# R002B.net
KiCad netlist of a schematic drawn in EAGLE
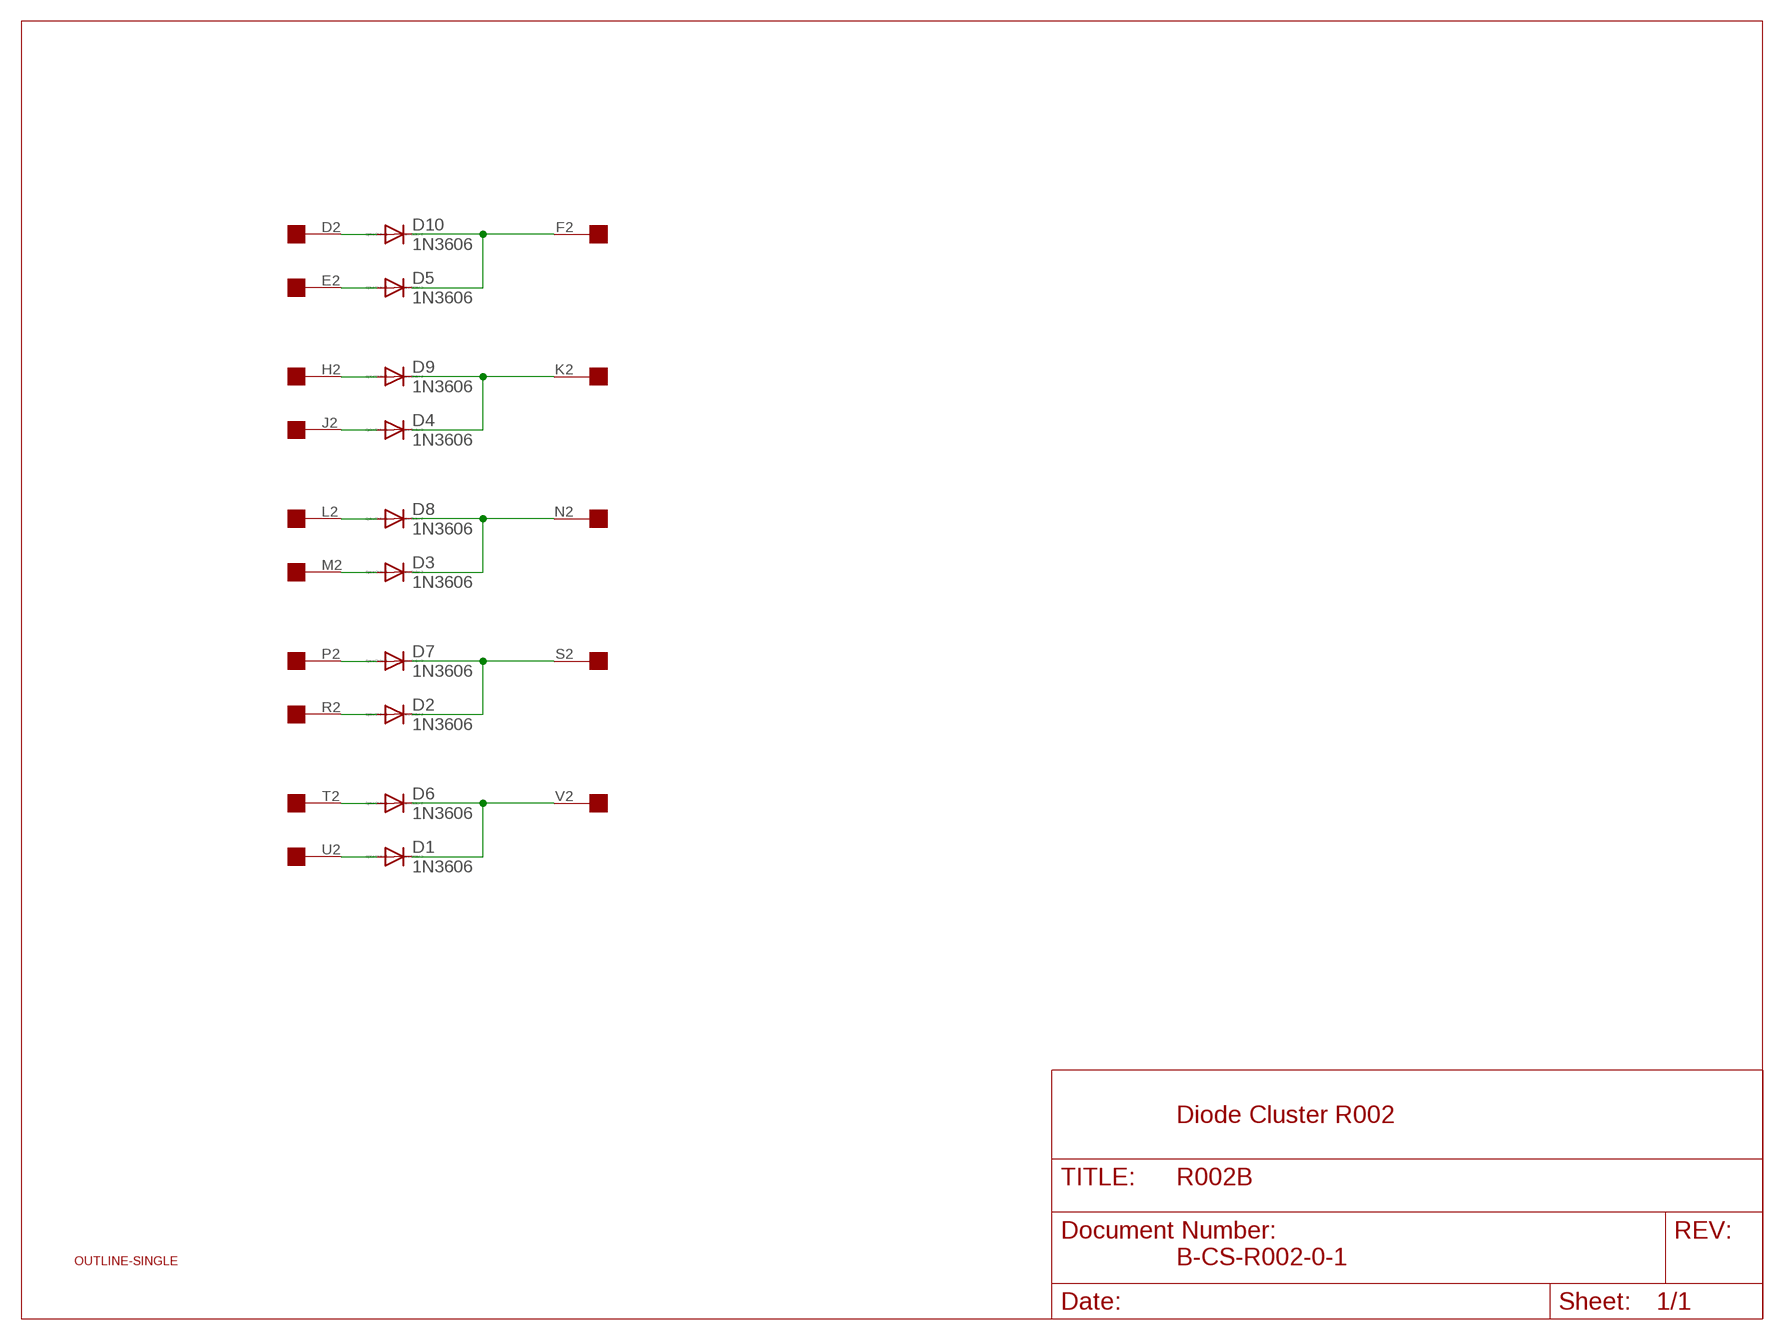
[diagram p0: schematic, sheet 1]

(export (version "E")
  (design (tool "Eeschema 10.0.6"))
  (components
    (comp (ref "D1")
      (value "1N3606")
      (footprint "eagle-import:DO35-10")
      (libsource (lib "eagle-import") (part "1N4148DO35-10"))
    )
    (comp (ref "D2")
      (value "1N3606")
      (footprint "eagle-import:DO35-10")
      (libsource (lib "eagle-import") (part "1N4148DO35-10"))
    )
    (comp (ref "D3")
      (value "1N3606")
      (footprint "eagle-import:DO35-10")
      (libsource (lib "eagle-import") (part "1N4148DO35-10"))
    )
    (comp (ref "D4")
      (value "1N3606")
      (footprint "eagle-import:DO35-10")
      (libsource (lib "eagle-import") (part "1N4148DO35-10"))
    )
    (comp (ref "D5")
      (value "1N3606")
      (footprint "eagle-import:DO35-10")
      (libsource (lib "eagle-import") (part "1N4148DO35-10"))
    )
    (comp (ref "D6")
      (value "1N3606")
      (footprint "eagle-import:DO35-10")
      (libsource (lib "eagle-import") (part "1N4148DO35-10"))
    )
    (comp (ref "D7")
      (value "1N3606")
      (footprint "eagle-import:DO35-10")
      (libsource (lib "eagle-import") (part "1N4148DO35-10"))
    )
    (comp (ref "D8")
      (value "1N3606")
      (footprint "eagle-import:DO35-10")
      (libsource (lib "eagle-import") (part "1N4148DO35-10"))
    )
    (comp (ref "D9")
      (value "1N3606")
      (footprint "eagle-import:DO35-10")
      (libsource (lib "eagle-import") (part "1N4148DO35-10"))
    )
    (comp (ref "D10")
      (value "1N3606")
      (footprint "eagle-import:DO35-10")
      (libsource (lib "eagle-import") (part "1N4148DO35-10"))
    )
    (comp (ref "U$1")
      (value "OUTLINE-SINGLE")
      (footprint "eagle-import:SINGLE")
      (libsource (lib "eagle-import") (part "OUTLINE-SINGLE"))
    )
    (comp (ref "U$2")
      (value "EDGE-1")
      (footprint "eagle-import:EDGE-CON1")
      (libsource (lib "eagle-import") (part "EDGE-1"))
    )
  )
  (nets
    (net (code "1") (name "Net-(U$2D-1)") (class "Default")
      (node (ref "D10") (pin "A") (pinfunction "A_A") (pintype "passive"))
      (node (ref "U$2") (pin "D2") (pinfunction "1_D2") (pintype "bidirectional"))
    )
    (net (code "2") (name "Net-(U$2E-1)") (class "Default")
      (node (ref "D5") (pin "A") (pinfunction "A_A") (pintype "passive"))
      (node (ref "U$2") (pin "E2") (pinfunction "1_E2") (pintype "bidirectional"))
    )
    (net (code "3") (name "Net-(U$2F-1)") (class "Default")
      (node (ref "D10") (pin "C") (pinfunction "C_C") (pintype "passive"))
      (node (ref "D5") (pin "C") (pinfunction "C_C") (pintype "passive"))
      (node (ref "U$2") (pin "F2") (pinfunction "1_F2") (pintype "bidirectional"))
    )
    (net (code "4") (name "Net-(U$2G-1)") (class "Default")
      (node (ref "D9") (pin "A") (pinfunction "A_A") (pintype "passive"))
      (node (ref "U$2") (pin "H2") (pinfunction "1_H2") (pintype "bidirectional"))
    )
    (net (code "5") (name "Net-(U$2H-1)") (class "Default")
      (node (ref "D4") (pin "A") (pinfunction "A_A") (pintype "passive"))
      (node (ref "U$2") (pin "J2") (pinfunction "1_J2") (pintype "bidirectional"))
    )
    (net (code "6") (name "Net-(U$2I-1)") (class "Default")
      (node (ref "D4") (pin "C") (pinfunction "C_C") (pintype "passive"))
      (node (ref "D9") (pin "C") (pinfunction "C_C") (pintype "passive"))
      (node (ref "U$2") (pin "K2") (pinfunction "1_K2") (pintype "bidirectional"))
    )
    (net (code "7") (name "Net-(U$2J-1)") (class "Default")
      (node (ref "D8") (pin "A") (pinfunction "A_A") (pintype "passive"))
      (node (ref "U$2") (pin "L2") (pinfunction "1_L2") (pintype "bidirectional"))
    )
    (net (code "8") (name "Net-(U$2K-1)") (class "Default")
      (node (ref "D3") (pin "A") (pinfunction "A_A") (pintype "passive"))
      (node (ref "U$2") (pin "M2") (pinfunction "1_M2") (pintype "bidirectional"))
    )
    (net (code "9") (name "Net-(U$2L-1)") (class "Default")
      (node (ref "D3") (pin "C") (pinfunction "C_C") (pintype "passive"))
      (node (ref "D8") (pin "C") (pinfunction "C_C") (pintype "passive"))
      (node (ref "U$2") (pin "N2") (pinfunction "1_N2") (pintype "bidirectional"))
    )
    (net (code "10") (name "Net-(U$2M-1)") (class "Default")
      (node (ref "D7") (pin "A") (pinfunction "A_A") (pintype "passive"))
      (node (ref "U$2") (pin "P2") (pinfunction "1_P2") (pintype "bidirectional"))
    )
    (net (code "11") (name "Net-(U$2N-1)") (class "Default")
      (node (ref "D2") (pin "A") (pinfunction "A_A") (pintype "passive"))
      (node (ref "U$2") (pin "R2") (pinfunction "1_R2") (pintype "bidirectional"))
    )
    (net (code "12") (name "Net-(U$2O-1)") (class "Default")
      (node (ref "D2") (pin "C") (pinfunction "C_C") (pintype "passive"))
      (node (ref "D7") (pin "C") (pinfunction "C_C") (pintype "passive"))
      (node (ref "U$2") (pin "S2") (pinfunction "1_S2") (pintype "bidirectional"))
    )
    (net (code "13") (name "Net-(U$2P-1)") (class "Default")
      (node (ref "D6") (pin "A") (pinfunction "A_A") (pintype "passive"))
      (node (ref "U$2") (pin "T2") (pinfunction "1_T2") (pintype "bidirectional"))
    )
    (net (code "14") (name "Net-(U$2Q-1)") (class "Default")
      (node (ref "D1") (pin "A") (pinfunction "A_A") (pintype "passive"))
      (node (ref "U$2") (pin "U2") (pinfunction "1_U2") (pintype "bidirectional"))
    )
    (net (code "15") (name "Net-(U$2R-1)") (class "Default")
      (node (ref "D1") (pin "C") (pinfunction "C_C") (pintype "passive"))
      (node (ref "D6") (pin "C") (pinfunction "C_C") (pintype "passive"))
      (node (ref "U$2") (pin "V2") (pinfunction "1_V2") (pintype "bidirectional"))
    )
  )
)
